# T14_SuperDuperRev2.net
KiCad netlist of a schematic drawn in EAGLE
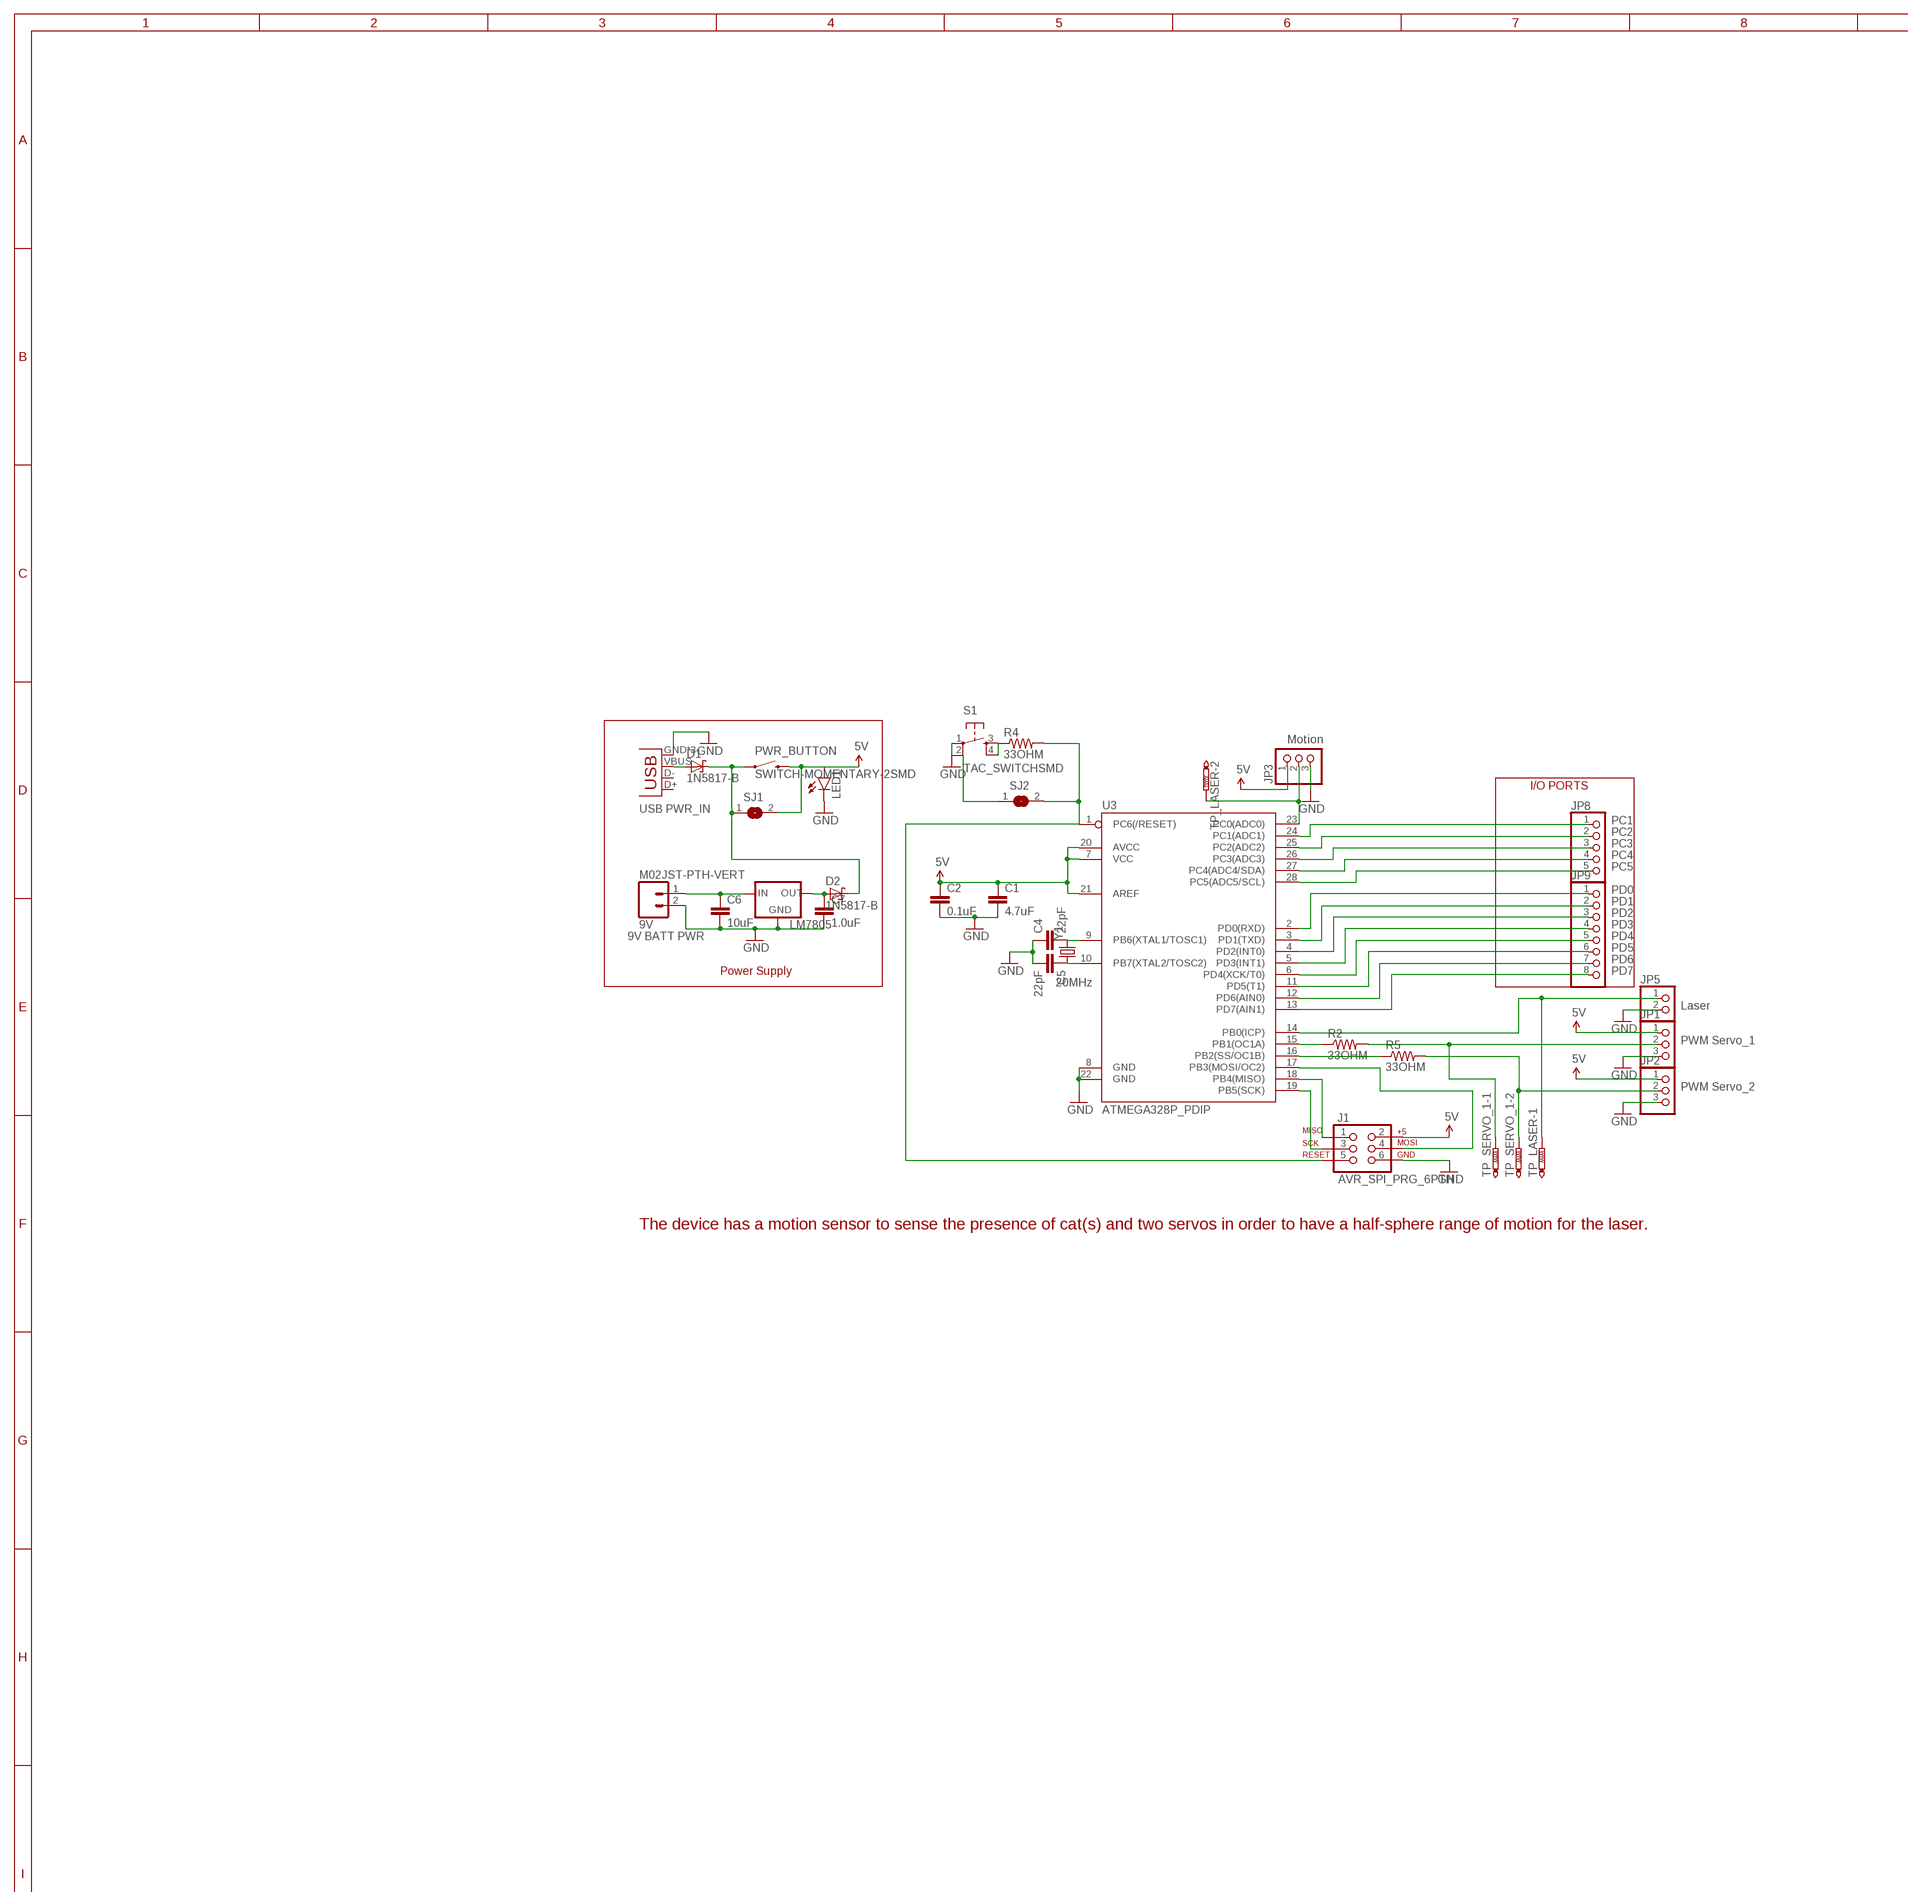
[diagram p0: schematic, sheet 1, part 1 of 2]
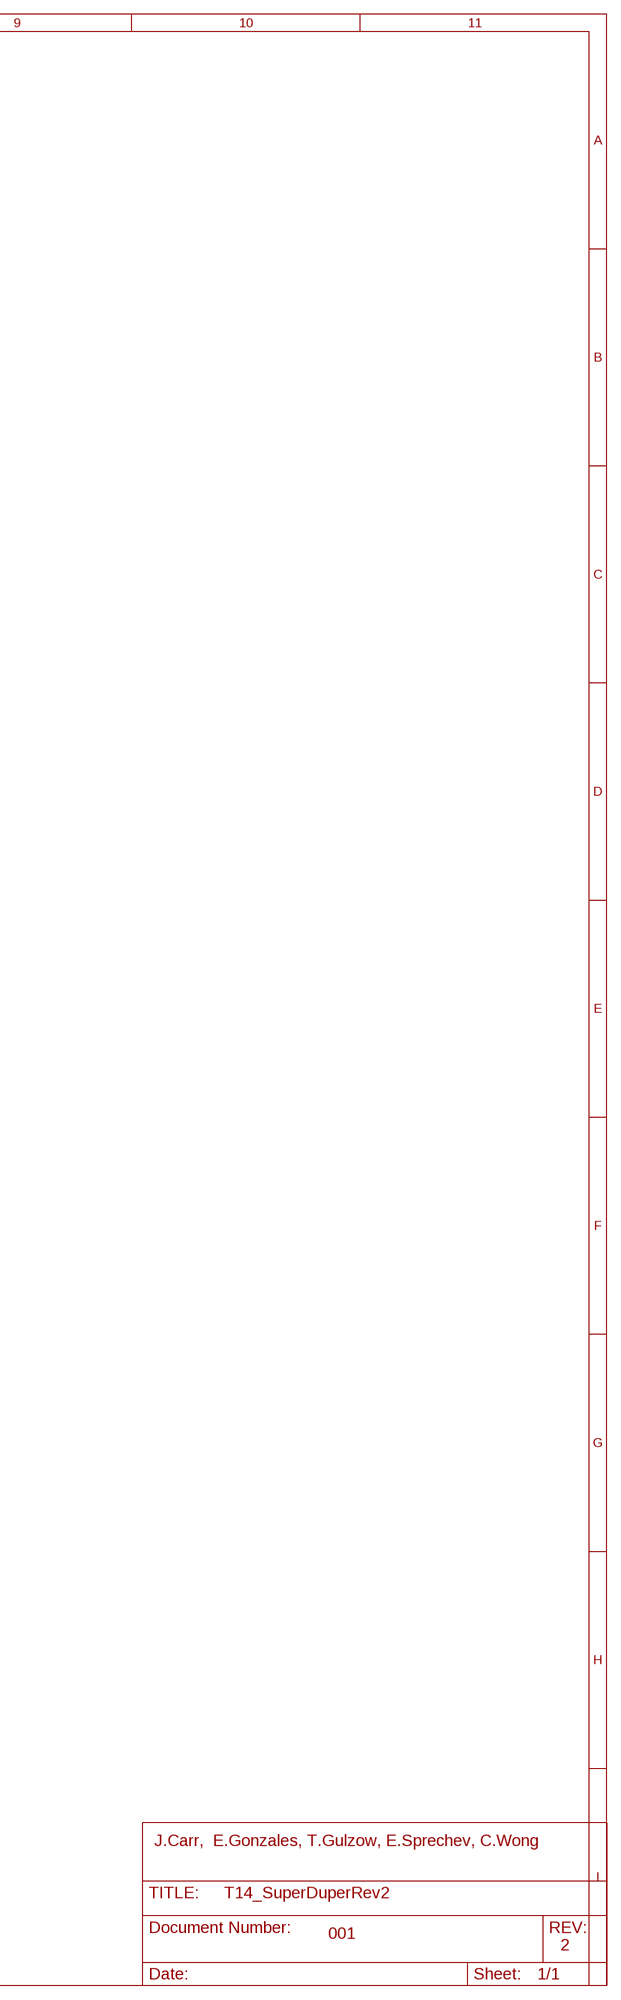
[diagram p1: schematic, sheet 1, part 2 of 2]

(export (version "E")
  (design (tool "Eeschema 10.0.6"))
  (components
    (comp (ref "9V")
      (value "M02JST-PTH-VERT")
      (footprint "eagle-import:JST-2-PTH-VERT")
      (libsource (lib "eagle-import") (part "M02JST-PTH-VERT"))
    )
    (comp (ref "C1")
      (value "4.7uF")
      (footprint "eagle-import:0603-CAP")
      (libsource (lib "eagle-import") (part "4.7UF-6.3V-10%(0603)0603"))
    )
    (comp (ref "C2")
      (value "0.1uF")
      (footprint "eagle-import:0603-CAP")
      (libsource (lib "eagle-import") (part "0.1UF-25V(+80/-20%)(0603)"))
    )
    (comp (ref "C4")
      (value "22pF")
      (footprint "eagle-import:0603-CAP")
      (libsource (lib "eagle-import") (part "4.7UF-6.3V-10%(0603)0603"))
    )
    (comp (ref "C5")
      (value "22pF")
      (footprint "eagle-import:0603-CAP")
      (libsource (lib "eagle-import") (part "4.7UF-6.3V-10%(0603)0603"))
    )
    (comp (ref "C6")
      (value "10uF")
      (footprint "eagle-import:0402-CAP")
      (libsource (lib "eagle-import") (part "1.0UF-16V-10%(0402)"))
    )
    (comp (ref "C7")
      (value "1.0uF")
      (footprint "eagle-import:0402-CAP")
      (libsource (lib "eagle-import") (part "1.0UF-16V-10%(0402)"))
    )
    (comp (ref "D1")
      (value "1N5817-B")
      (footprint "eagle-import:DO41-7.6")
      (libsource (lib "eagle-import") (part "1N5817-B"))
    )
    (comp (ref "D2")
      (value "1N5817-B")
      (footprint "eagle-import:DO41-7.6")
      (libsource (lib "eagle-import") (part "1N5817-B"))
    )
    (comp (ref "J1")
      (value "AVR_SPI_PRG_6PTH")
      (footprint "eagle-import:2X3")
      (libsource (lib "eagle-import") (part "AVR_SPI_PRG_6PTH"))
    )
    (comp (ref "JP1")
      (value "PINHD-1X3")
      (footprint "eagle-import:1X03")
      (libsource (lib "eagle-import") (part "PINHD-1X3"))
    )
    (comp (ref "JP2")
      (value "PINHD-1X3")
      (footprint "eagle-import:1X03")
      (libsource (lib "eagle-import") (part "PINHD-1X3"))
    )
    (comp (ref "JP3")
      (value "PINHD-1X3")
      (footprint "eagle-import:1X03")
      (libsource (lib "eagle-import") (part "PINHD-1X3"))
    )
    (comp (ref "JP4")
      (value "USB-MICROB")
      (footprint "eagle-import:USB-MICROB")
      (libsource (lib "eagle-import") (part "USB-MICROB"))
    )
    (comp (ref "JP5")
      (value "PINHD-1X2")
      (footprint "eagle-import:1X02")
      (libsource (lib "eagle-import") (part "PINHD-1X2"))
    )
    (comp (ref "JP8")
      (value "PINHD-1X5")
      (footprint "eagle-import:1X05")
      (libsource (lib "eagle-import") (part "PINHD-1X5"))
    )
    (comp (ref "JP9")
      (value "PINHD-1X8")
      (footprint "eagle-import:1X08")
      (libsource (lib "eagle-import") (part "PINHD-1X8"))
    )
    (comp (ref "LED1")
      (value "LED-3MM-NO_SILK")
      (footprint "eagle-import:LED3MM-NS")
      (libsource (lib "eagle-import") (part "LED-3MM-NO_SILK"))
    )
    (comp (ref "LM7805")
      (value "V_REG_78XXSIDE")
      (footprint "eagle-import:78XXL")
      (libsource (lib "eagle-import") (part "V_REG_78XXSIDE"))
    )
    (comp (ref "PWR_BUTTON")
      (value "SWITCH-MOMENTARY-2SMD")
      (footprint "eagle-import:TACTILE-SWITCH-SMD")
      (libsource (lib "eagle-import") (part "SWITCH-MOMENTARY-2SMD"))
    )
    (comp (ref "R2")
      (value "33OHM")
      (footprint "eagle-import:0603")
      (libsource (lib "eagle-import") (part "33OHM1/10W1%(0603)"))
    )
    (comp (ref "R4")
      (value "33OHM")
      (footprint "eagle-import:0603")
      (libsource (lib "eagle-import") (part "33OHM1/10W1%(0603)"))
    )
    (comp (ref "R5")
      (value "33OHM")
      (footprint "eagle-import:0603")
      (libsource (lib "eagle-import") (part "33OHM1/10W1%(0603)"))
    )
    (comp (ref "S1")
      (value "TAC_SWITCHSMD")
      (footprint "eagle-import:TACTILE-SWITCH-SMD")
      (libsource (lib "eagle-import") (part "TAC_SWITCHSMD"))
    )
    (comp (ref "SJ1") (value "SJ") (footprint "eagle-import:SJ") (libsource (lib "eagle-import") (part "SJ")))
    (comp (ref "SJ2") (value "SJ") (footprint "eagle-import:SJ") (libsource (lib "eagle-import") (part "SJ")))
    (comp (ref "TP_LASER")
      (value "PTR2")
      (footprint "eagle-import:P2-38-17")
      (libsource (lib "eagle-import") (part "PTR2"))
    )
    (comp (ref "TP_SERVO_1")
      (value "PTR2")
      (footprint "eagle-import:P2-38-17")
      (libsource (lib "eagle-import") (part "PTR2"))
    )
    (comp (ref "U3")
      (value "ATMEGA328P_PDIP")
      (footprint "eagle-import:DIL28-3")
      (libsource (lib "eagle-import") (part "ATMEGA328P_PDIP"))
    )
    (comp (ref "Y1")
      (value "CRYSTAL10.5X4.8")
      (footprint "eagle-import:CRYSTAL-SMD-10.5X4.8-2PIN")
      (libsource (lib "eagle-import") (part "CRYSTAL10.5X4.8"))
    )
  )
  (nets
    (net (code "1") (name "5V") (class "Default")
      (node (ref "C1") (pin "1") (pinfunction "1_1") (pintype "passive"))
      (node (ref "C2") (pin "1") (pinfunction "1_1") (pintype "passive"))
      (node (ref "J1") (pin "2") (pinfunction "2_2") (pintype "passive"))
      (node (ref "JP1") (pin "1") (pinfunction "1_1") (pintype "passive"))
      (node (ref "JP2") (pin "1") (pinfunction "1_1") (pintype "passive"))
      (node (ref "JP3") (pin "1") (pinfunction "1_1") (pintype "passive"))
      (node (ref "LED1") (pin "A") (pinfunction "A_A") (pintype "passive"))
      (node (ref "PWR_BUTTON") (pin "3") (pinfunction "2_3") (pintype "passive"))
      (node (ref "SJ1") (pin "2") (pinfunction "2_2") (pintype "passive"))
      (node (ref "U3") (pin "20") (pinfunction "AVCC_20") (pintype "bidirectional"))
      (node (ref "U3") (pin "21") (pinfunction "AREF_21") (pintype "bidirectional"))
      (node (ref "U3") (pin "7") (pinfunction "VCC_7") (pintype "bidirectional"))
    )
    (net (code "2") (name "GND") (class "Default")
      (node (ref "9V") (pin "2") (pinfunction "2_2") (pintype "passive"))
      (node (ref "C1") (pin "2") (pinfunction "2_2") (pintype "passive"))
      (node (ref "C2") (pin "2") (pinfunction "2_2") (pintype "passive"))
      (node (ref "C4") (pin "1") (pinfunction "1_1") (pintype "passive"))
      (node (ref "C5") (pin "2") (pinfunction "2_2") (pintype "passive"))
      (node (ref "C6") (pin "2") (pinfunction "2_2") (pintype "passive"))
      (node (ref "C7") (pin "2") (pinfunction "2_2") (pintype "passive"))
      (node (ref "J1") (pin "6") (pinfunction "6_6") (pintype "passive"))
      (node (ref "JP1") (pin "3") (pinfunction "3_3") (pintype "passive"))
      (node (ref "JP2") (pin "3") (pinfunction "3_3") (pintype "passive"))
      (node (ref "JP3") (pin "3") (pinfunction "3_3") (pintype "passive"))
      (node (ref "JP4") (pin "GND") (pinfunction "GND_GND") (pintype "bidirectional"))
      (node (ref "JP4") (pin "MT1") (pinfunction "GND_MT1") (pintype "bidirectional"))
      (node (ref "JP4") (pin "MT2") (pinfunction "GND_MT2") (pintype "bidirectional"))
      (node (ref "JP5") (pin "2") (pinfunction "2_2") (pintype "passive"))
      (node (ref "LED1") (pin "K") (pinfunction "C_K") (pintype "passive"))
      (node (ref "LM7805") (pin "GND") (pinfunction "GND_GND") (pintype "input"))
      (node (ref "S1") (pin "1") (pinfunction "1_1") (pintype "passive"))
      (node (ref "S1") (pin "2") (pinfunction "2_2") (pintype "passive"))
      (node (ref "U3") (pin "22") (pinfunction "GND_22") (pintype "bidirectional"))
      (node (ref "U3") (pin "8") (pinfunction "GND_8") (pintype "bidirectional"))
    )
    (net (code "3") (name "Net-(9V-Pad1)") (class "Default")
      (node (ref "9V") (pin "1") (pinfunction "1_1") (pintype "passive"))
      (node (ref "C6") (pin "1") (pinfunction "1_1") (pintype "passive"))
      (node (ref "LM7805") (pin "IN") (pinfunction "IN_IN") (pintype "input"))
    )
    (net (code "4") (name "Net-(C7-Pad1)") (class "Default")
      (node (ref "C7") (pin "1") (pinfunction "1_1") (pintype "passive"))
      (node (ref "D2") (pin "A") (pinfunction "A_A") (pintype "passive"))
      (node (ref "LM7805") (pin "OUT") (pinfunction "OUT_OUT") (pintype "output"))
    )
    (net (code "5") (name "Net-(D1-PadA)") (class "Default")
      (node (ref "D1") (pin "A") (pinfunction "A_A") (pintype "passive"))
      (node (ref "JP4") (pin "VBUS") (pinfunction "VBUS_VBUS") (pintype "bidirectional"))
    )
    (net (code "6") (name "Net-(D1-PadC)") (class "Default")
      (node (ref "D1") (pin "C") (pinfunction "C_C") (pintype "passive"))
      (node (ref "D2") (pin "C") (pinfunction "C_C") (pintype "passive"))
      (node (ref "PWR_BUTTON") (pin "1") (pinfunction "1_1") (pintype "passive"))
      (node (ref "SJ1") (pin "1") (pinfunction "1_1") (pintype "passive"))
    )
    (net (code "7") (name "Net-(R4-Pad1)") (class "Default")
      (node (ref "R4") (pin "1") (pinfunction "1_1") (pintype "passive"))
      (node (ref "S1") (pin "3") (pinfunction "3_3") (pintype "passive"))
      (node (ref "S1") (pin "4") (pinfunction "4_4") (pintype "passive"))
    )
    (net (code "8") (name "Net-(TP_LASERA-TP)") (class "Default")
      (node (ref "JP5") (pin "1") (pinfunction "1_1") (pintype "passive"))
      (node (ref "TP_LASER") (pin "TP-1") (pinfunction "TP_TP-1") (pintype "input"))
      (node (ref "U3") (pin "14") (pinfunction "PB0(ICP)_14") (pintype "bidirectional"))
    )
    (net (code "9") (name "Net-(TP_LASERB-TP)") (class "Default")
      (node (ref "JP3") (pin "2") (pinfunction "2_2") (pintype "passive"))
      (node (ref "TP_LASER") (pin "TP-2") (pinfunction "TP_TP-2") (pintype "input"))
      (node (ref "U3") (pin "23") (pinfunction "PC0(ADC0)_23") (pintype "bidirectional"))
    )
    (net (code "10") (name "Net-(TP_SERVO_1A-TP)") (class "Default")
      (node (ref "JP1") (pin "2") (pinfunction "2_2") (pintype "passive"))
      (node (ref "R2") (pin "2") (pinfunction "2_2") (pintype "passive"))
      (node (ref "TP_SERVO_1") (pin "TP-1") (pinfunction "TP_TP-1") (pintype "input"))
    )
    (net (code "11") (name "Net-(TP_SERVO_1B-TP)") (class "Default")
      (node (ref "JP2") (pin "2") (pinfunction "2_2") (pintype "passive"))
      (node (ref "R5") (pin "2") (pinfunction "2_2") (pintype "passive"))
      (node (ref "TP_SERVO_1") (pin "TP-2") (pinfunction "TP_TP-2") (pintype "input"))
    )
    (net (code "12") (name "Net-(U3-PB1(OC1A))") (class "Default")
      (node (ref "R2") (pin "1") (pinfunction "1_1") (pintype "passive"))
      (node (ref "U3") (pin "15") (pinfunction "PB1(OC1A)_15") (pintype "bidirectional"))
    )
    (net (code "13") (name "Net-(U3-PB2(SS{slash}OC1B))") (class "Default")
      (node (ref "R5") (pin "1") (pinfunction "1_1") (pintype "passive"))
      (node (ref "U3") (pin "16") (pinfunction "PB2(SS/OC1B)_16") (pintype "bidirectional"))
    )
    (net (code "14") (name "Net-(U3-PB3(MOSI{slash}OC2))") (class "Default")
      (node (ref "J1") (pin "4") (pinfunction "4_4") (pintype "passive"))
      (node (ref "U3") (pin "17") (pinfunction "PB3(MOSI/OC2)_17") (pintype "bidirectional"))
    )
    (net (code "15") (name "Net-(U3-PB4(MISO))") (class "Default")
      (node (ref "J1") (pin "1") (pinfunction "1_1") (pintype "passive"))
      (node (ref "U3") (pin "18") (pinfunction "PB4(MISO)_18") (pintype "bidirectional"))
    )
    (net (code "16") (name "Net-(U3-PB5(SCK))") (class "Default")
      (node (ref "J1") (pin "3") (pinfunction "3_3") (pintype "passive"))
      (node (ref "U3") (pin "19") (pinfunction "PB5(SCK)_19") (pintype "bidirectional"))
    )
    (net (code "17") (name "Net-(U3-PB6(XTAL1{slash}TOSC1))") (class "Default")
      (node (ref "C4") (pin "2") (pinfunction "2_2") (pintype "passive"))
      (node (ref "U3") (pin "9") (pinfunction "PB6(XTAL1/TOSC1)_9") (pintype "bidirectional"))
      (node (ref "Y1") (pin "P$2") (pinfunction "2_P$2") (pintype "passive"))
    )
    (net (code "18") (name "Net-(U3-PB7(XTAL2{slash}TOSC2))") (class "Default")
      (node (ref "C5") (pin "1") (pinfunction "1_1") (pintype "passive"))
      (node (ref "U3") (pin "10") (pinfunction "PB7(XTAL2/TOSC2)_10") (pintype "bidirectional"))
      (node (ref "Y1") (pin "P$1") (pinfunction "1_P$1") (pintype "passive"))
    )
    (net (code "19") (name "Net-(U3-PC1(ADC1))") (class "Default")
      (node (ref "JP8") (pin "1") (pinfunction "1_1") (pintype "passive"))
      (node (ref "U3") (pin "24") (pinfunction "PC1(ADC1)_24") (pintype "bidirectional"))
    )
    (net (code "20") (name "Net-(U3-PC2(ADC2))") (class "Default")
      (node (ref "JP8") (pin "2") (pinfunction "2_2") (pintype "passive"))
      (node (ref "U3") (pin "25") (pinfunction "PC2(ADC2)_25") (pintype "bidirectional"))
    )
    (net (code "21") (name "Net-(U3-PC3(ADC3))") (class "Default")
      (node (ref "JP8") (pin "3") (pinfunction "3_3") (pintype "passive"))
      (node (ref "U3") (pin "26") (pinfunction "PC3(ADC3)_26") (pintype "bidirectional"))
    )
    (net (code "22") (name "Net-(U3-PC4(ADC4{slash}SDA))") (class "Default")
      (node (ref "JP8") (pin "4") (pinfunction "4_4") (pintype "passive"))
      (node (ref "U3") (pin "27") (pinfunction "PC4(ADC4/SDA)_27") (pintype "bidirectional"))
    )
    (net (code "23") (name "Net-(U3-PC5(ADC5{slash}SCL))") (class "Default")
      (node (ref "JP8") (pin "5") (pinfunction "5_5") (pintype "passive"))
      (node (ref "U3") (pin "28") (pinfunction "PC5(ADC5/SCL)_28") (pintype "bidirectional"))
    )
    (net (code "24") (name "Net-(U3-PC6({slash}RESET))") (class "Default")
      (node (ref "J1") (pin "5") (pinfunction "5_5") (pintype "passive"))
      (node (ref "R4") (pin "2") (pinfunction "2_2") (pintype "passive"))
      (node (ref "SJ2") (pin "2") (pinfunction "2_2") (pintype "passive"))
      (node (ref "U3") (pin "1") (pinfunction "PC6(/RESET)_1") (pintype "bidirectional"))
    )
    (net (code "25") (name "Net-(U3-PD0(RXD))") (class "Default")
      (node (ref "JP9") (pin "1") (pinfunction "1_1") (pintype "passive"))
      (node (ref "U3") (pin "2") (pinfunction "PD0(RXD)_2") (pintype "bidirectional"))
    )
    (net (code "26") (name "Net-(U3-PD1(TXD))") (class "Default")
      (node (ref "JP9") (pin "2") (pinfunction "2_2") (pintype "passive"))
      (node (ref "U3") (pin "3") (pinfunction "PD1(TXD)_3") (pintype "bidirectional"))
    )
    (net (code "27") (name "Net-(U3-PD2(INT0))") (class "Default")
      (node (ref "JP9") (pin "3") (pinfunction "3_3") (pintype "passive"))
      (node (ref "U3") (pin "4") (pinfunction "PD2(INT0)_4") (pintype "bidirectional"))
    )
    (net (code "28") (name "Net-(U3-PD3(INT1))") (class "Default")
      (node (ref "JP9") (pin "4") (pinfunction "4_4") (pintype "passive"))
      (node (ref "U3") (pin "5") (pinfunction "PD3(INT1)_5") (pintype "bidirectional"))
    )
    (net (code "29") (name "Net-(U3-PD4(XCK{slash}T0))") (class "Default")
      (node (ref "JP9") (pin "5") (pinfunction "5_5") (pintype "passive"))
      (node (ref "U3") (pin "6") (pinfunction "PD4(XCK/T0)_6") (pintype "bidirectional"))
    )
    (net (code "30") (name "Net-(U3-PD5(T1))") (class "Default")
      (node (ref "JP9") (pin "6") (pinfunction "6_6") (pintype "passive"))
      (node (ref "U3") (pin "11") (pinfunction "PD5(T1)_11") (pintype "bidirectional"))
    )
    (net (code "31") (name "Net-(U3-PD6(AIN0))") (class "Default")
      (node (ref "JP9") (pin "7") (pinfunction "7_7") (pintype "passive"))
      (node (ref "U3") (pin "12") (pinfunction "PD6(AIN0)_12") (pintype "bidirectional"))
    )
    (net (code "32") (name "Net-(U3-PD7(AIN1))") (class "Default")
      (node (ref "JP9") (pin "8") (pinfunction "8_8") (pintype "passive"))
      (node (ref "U3") (pin "13") (pinfunction "PD7(AIN1)_13") (pintype "bidirectional"))
    )
    (net (code "33") (name "unconnected-(JP4-PadD+)") (class "Default")
      (node (ref "JP4") (pin "D+") (pinfunction "D+_D+") (pintype "bidirectional"))
    )
    (net (code "34") (name "unconnected-(JP4-PadD-)") (class "Default")
      (node (ref "JP4") (pin "D-") (pinfunction "D-_D-") (pintype "bidirectional"))
    )
    (net (code "35") (name "unconnected-(SJ2-Pad1)") (class "Default")
      (node (ref "SJ2") (pin "1") (pinfunction "1_1") (pintype "passive"))
    )
  )
)
